# Ring_Controller.net
KiCad netlist of a schematic drawn in EAGLE
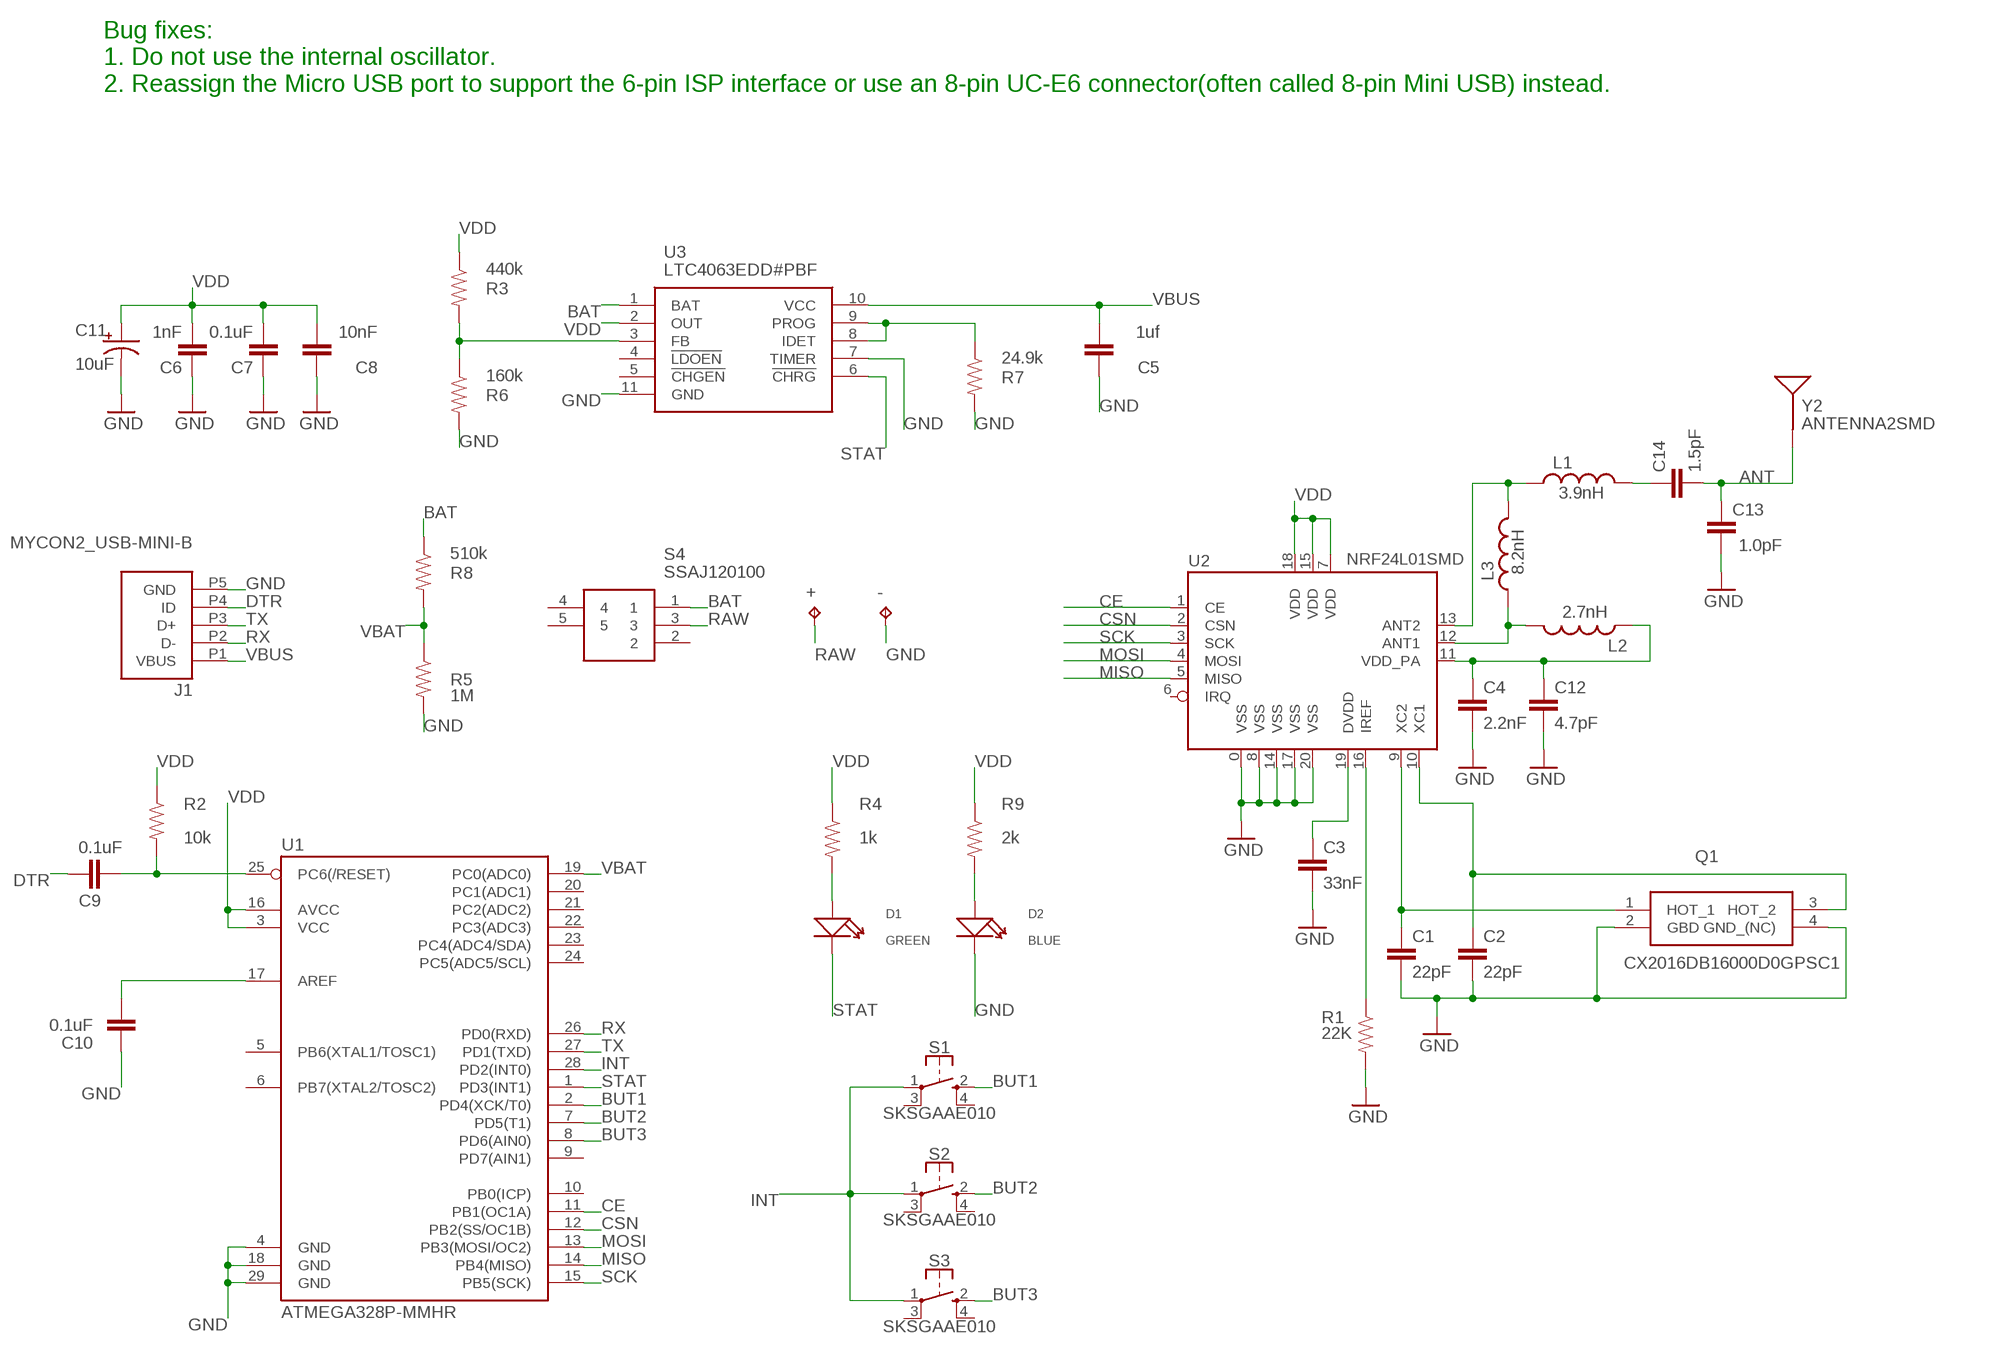
[diagram p0: schematic, sheet 1]

(export (version "E")
  (design (tool "Eeschema 10.0.6"))
  (components
    (comp (ref "+")
      (value "TPB1,27")
      (footprint "eagle-import:B1,27")
      (libsource (lib "eagle-import") (part "TPB1,27"))
    )
    (comp (ref "-")
      (value "TPB1,27")
      (footprint "eagle-import:B1,27")
      (libsource (lib "eagle-import") (part "TPB1,27"))
    )
    (comp (ref "C1")
      (value "22pF")
      (footprint "eagle-import:0402-CAP")
      (libsource (lib "eagle-import") (part "CAP0402-CAP"))
    )
    (comp (ref "C2")
      (value "22pF")
      (footprint "eagle-import:0402-CAP")
      (libsource (lib "eagle-import") (part "CAP0402-CAP"))
    )
    (comp (ref "C3")
      (value "33nF")
      (footprint "eagle-import:0402-CAP")
      (libsource (lib "eagle-import") (part "CAP0402-CAP"))
    )
    (comp (ref "C4")
      (value "2.2nF")
      (footprint "eagle-import:0402-CAP")
      (libsource (lib "eagle-import") (part "CAP0402-CAP"))
    )
    (comp (ref "C5")
      (value "1uf")
      (footprint "eagle-import:0402-CAP")
      (libsource (lib "eagle-import") (part "SparkFun-Passives_CAP0402-CAP"))
    )
    (comp (ref "C6")
      (value "1nF")
      (footprint "eagle-import:0402-CAP")
      (libsource (lib "eagle-import") (part "SparkFun-Passives_CAP0402-CAP"))
    )
    (comp (ref "C7")
      (value "0.1uF")
      (footprint "eagle-import:0402-CAP")
      (libsource (lib "eagle-import") (part "SparkFun-Passives_CAP0402-CAP"))
    )
    (comp (ref "C8")
      (value "10nF")
      (footprint "eagle-import:0402-CAP")
      (libsource (lib "eagle-import") (part "SparkFun-Passives_CAP0402-CAP"))
    )
    (comp (ref "C9")
      (value "0.1uF")
      (footprint "eagle-import:0402-CAP")
      (libsource (lib "eagle-import") (part "SparkFun-Passives_CAP0402-CAP"))
    )
    (comp (ref "C10")
      (value "0.1uF")
      (footprint "eagle-import:0402-CAP")
      (libsource (lib "eagle-import") (part "SparkFun-Passives_CAP0402-CAP"))
    )
    (comp (ref "C11")
      (value "10uF")
      (footprint "eagle-import:0603-POLAR")
      (libsource (lib "eagle-import") (part "10UF-POLAR-0603-6.3V-20%(TANT)"))
    )
    (comp (ref "C12")
      (value "4.7pF")
      (footprint "eagle-import:0402-CAP")
      (libsource (lib "eagle-import") (part "CAP0402-CAP"))
    )
    (comp (ref "C13")
      (value "1.0pF")
      (footprint "eagle-import:0402-CAP")
      (libsource (lib "eagle-import") (part "CAP0402-CAP"))
    )
    (comp (ref "C14")
      (value "1.5pF")
      (footprint "eagle-import:0402-CAP")
      (libsource (lib "eagle-import") (part "CAP0402-CAP"))
    )
    (comp (ref "D1")
      (value "GREEN")
      (footprint "eagle-import:LED-0402")
      (fields (field (name "MPN") "BL-HB337A-AV-TRB"))
      (libsource (lib "eagle-import") (part "SMD-LED-CLEAR-BLUE(0402)"))
    )
    (comp (ref "D2")
      (value "BLUE")
      (footprint "eagle-import:LED-0402")
      (fields (field (name "MPN") "BL-HB337A-AV-TRB"))
      (libsource (lib "eagle-import") (part "SMD-LED-CLEAR-BLUE(0402)"))
    )
    (comp (ref "J1")
      (value "MYCON2_USB-MINI-B")
      (footprint "eagle-import:CON2_USB_MICRO_B_AT")
      (fields (field (name "SPICEPREFIX") "X"))
      (libsource (lib "eagle-import") (part "MYCON2_USB-MINI-B"))
    )
    (comp (ref "L1")
      (value "3.9nH")
      (footprint "eagle-import:C0402")
      (libsource (lib "eagle-import") (part "INDUCTOR0402"))
    )
    (comp (ref "L2")
      (value "2.7nH")
      (footprint "eagle-import:C0402")
      (libsource (lib "eagle-import") (part "INDUCTOR0402"))
    )
    (comp (ref "L3")
      (value "8.2nH")
      (footprint "eagle-import:C0402")
      (libsource (lib "eagle-import") (part "INDUCTOR0402"))
    )
    (comp (ref "Q1")
      (value "CX2016DB16000D0GPSC1")
      (footprint "eagle-import:CX2016DB_1")
      (fields (field (name "MOUSER_PART_NUMBER") "581-CX2016DB16000DPS"))
      (libsource (lib "eagle-import") (part "CX2016DB16000D0GPSC1"))
    )
    (comp (ref "R1")
      (value "22K")
      (footprint "eagle-import:0402-RES")
      (libsource (lib "eagle-import") (part "RESISTOR0402-RES"))
    )
    (comp (ref "R2")
      (value "10k")
      (footprint "eagle-import:0402-RES")
      (libsource (lib "eagle-import") (part "RESISTOR0402"))
    )
    (comp (ref "R3")
      (value "440k")
      (footprint "eagle-import:0402-RES")
      (libsource (lib "eagle-import") (part "RESISTOR0402"))
    )
    (comp (ref "R4")
      (value "1k")
      (footprint "eagle-import:0402-RES")
      (libsource (lib "eagle-import") (part "RESISTOR0402"))
    )
    (comp (ref "R5")
      (value "1M")
      (footprint "eagle-import:0402-RES")
      (libsource (lib "eagle-import") (part "RESISTOR0402"))
    )
    (comp (ref "R6")
      (value "160k")
      (footprint "eagle-import:0402-RES")
      (libsource (lib "eagle-import") (part "RESISTOR0402"))
    )
    (comp (ref "R7")
      (value "24.9k")
      (footprint "eagle-import:0402-RES")
      (libsource (lib "eagle-import") (part "RESISTOR0402"))
    )
    (comp (ref "R8")
      (value "510k")
      (footprint "eagle-import:0402-RES")
      (libsource (lib "eagle-import") (part "RESISTOR0402"))
    )
    (comp (ref "R9")
      (value "2k")
      (footprint "eagle-import:0402-RES")
      (libsource (lib "eagle-import") (part "RESISTOR0402"))
    )
    (comp (ref "S1")
      (value "SKSGAAE010")
      (footprint "eagle-import:SKSG")
      (fields (field (name "MOUSER_PART_NUMBER") "688-SKSGAAE010"))
      (libsource (lib "eagle-import") (part "SKSGAAE010"))
    )
    (comp (ref "S2")
      (value "SKSGAAE010")
      (footprint "eagle-import:SKSG")
      (fields (field (name "MOUSER_PART_NUMBER") "688-SKSGAAE010"))
      (libsource (lib "eagle-import") (part "SKSGAAE010"))
    )
    (comp (ref "S3")
      (value "SKSGAAE010")
      (footprint "eagle-import:SKSG")
      (fields (field (name "MOUSER_PART_NUMBER") "688-SKSGAAE010"))
      (libsource (lib "eagle-import") (part "SKSGAAE010"))
    )
    (comp (ref "S4")
      (value "SSAJ120100")
      (footprint "eagle-import:SSAJ120100")
      (fields (field (name "MOUSER_PART_NUMBER") "688-SSAJ120100") (field (name "RS_PART_NUMBER") "1238892"))
      (libsource (lib "eagle-import") (part "SSAJ120100"))
    )
    (comp (ref "U1")
      (value "ATMEGA328P-MMHR")
      (footprint "eagle-import:QFN45P400X400X100-29N")
      (fields (field (name "MOUSER_PART_NUMBER") "556-ATMEGA328P-MMHR"))
      (libsource (lib "eagle-import") (part "ATMEGA328P-MMHR"))
    )
    (comp (ref "U2")
      (value "NRF24L01SMD")
      (footprint "eagle-import:QFN20-4X4MM")
      (libsource (lib "eagle-import") (part "NRF24L01SMD"))
    )
    (comp (ref "U3")
      (value "LTC4063EDD#PBF")
      (footprint "eagle-import:SON50P300X300X80-11N")
      (fields (field (name "MOUSER_PART_NUMBER") "584-LTC4063EDD#PBF"))
      (libsource (lib "eagle-import") (part "LTC4063EDD#PBF"))
    )
    (comp (ref "Y2")
      (value "ANTENNA2SMD")
      (footprint "eagle-import:ANTENNA-CHIP2")
      (libsource (lib "eagle-import") (part "ANTENNA2SMD"))
    )
  )
  (nets
    (net (code "1") (name "/ANT") (class "Default")
      (node (ref "C13") (pin "2") (pinfunction "2_2") (pintype "passive"))
      (node (ref "C14") (pin "2") (pinfunction "2_2") (pintype "passive"))
      (node (ref "Y2") (pin "FEED") (pinfunction "SIGNAL_FEED") (pintype "bidirectional"))
    )
    (net (code "2") (name "/BAT") (class "Default")
      (node (ref "R8") (pin "1") (pinfunction "1_1") (pintype "passive"))
      (node (ref "S4") (pin "1") (pinfunction "1_1") (pintype "bidirectional"))
      (node (ref "U3") (pin "1") (pinfunction "BAT_1") (pintype "bidirectional"))
    )
    (net (code "3") (name "/BUT1") (class "Default")
      (node (ref "S1") (pin "2") (pinfunction "3_2") (pintype "passive"))
      (node (ref "U1") (pin "2") (pinfunction "PD4(XCK/T0)_2") (pintype "bidirectional"))
    )
    (net (code "4") (name "/BUT2") (class "Default")
      (node (ref "S2") (pin "2") (pinfunction "3_2") (pintype "passive"))
      (node (ref "U1") (pin "7") (pinfunction "PD5(T1)_7") (pintype "bidirectional"))
    )
    (net (code "5") (name "/BUT3") (class "Default")
      (node (ref "S3") (pin "2") (pinfunction "3_2") (pintype "passive"))
      (node (ref "U1") (pin "8") (pinfunction "PD6(AIN0)_8") (pintype "bidirectional"))
    )
    (net (code "6") (name "/CE") (class "Default")
      (node (ref "U1") (pin "11") (pinfunction "PB1(OC1A)_11") (pintype "bidirectional"))
      (node (ref "U2") (pin "1") (pinfunction "CE_1") (pintype "input"))
    )
    (net (code "7") (name "/CSN") (class "Default")
      (node (ref "U1") (pin "12") (pinfunction "PB2(SS/OC1B)_12") (pintype "bidirectional"))
      (node (ref "U2") (pin "2") (pinfunction "CSN_2") (pintype "input"))
    )
    (net (code "8") (name "/DTR") (class "Default")
      (node (ref "C9") (pin "1") (pinfunction "1_1") (pintype "passive"))
      (node (ref "J1") (pin "P4") (pinfunction "ID_P4") (pintype "bidirectional"))
    )
    (net (code "9") (name "/INT") (class "Default")
      (node (ref "S1") (pin "1") (pinfunction "1_1") (pintype "passive"))
      (node (ref "S2") (pin "1") (pinfunction "1_1") (pintype "passive"))
      (node (ref "S3") (pin "1") (pinfunction "1_1") (pintype "passive"))
      (node (ref "U1") (pin "28") (pinfunction "PD2(INT0)_28") (pintype "bidirectional"))
    )
    (net (code "10") (name "/MISO") (class "Default")
      (node (ref "U1") (pin "14") (pinfunction "PB4(MISO)_14") (pintype "bidirectional"))
      (node (ref "U2") (pin "5") (pinfunction "MISO_5") (pintype "output"))
    )
    (net (code "11") (name "/MOSI") (class "Default")
      (node (ref "U1") (pin "13") (pinfunction "PB3(MOSI/OC2)_13") (pintype "bidirectional"))
      (node (ref "U2") (pin "4") (pinfunction "MOSI_4") (pintype "input"))
    )
    (net (code "12") (name "/RAW") (class "Default")
      (node (ref "+") (pin "TP") (pinfunction "TP_TP") (pintype "input"))
      (node (ref "S4") (pin "3") (pinfunction "3_3") (pintype "bidirectional"))
    )
    (net (code "13") (name "/RX") (class "Default")
      (node (ref "J1") (pin "P2") (pinfunction "D-_P2") (pintype "bidirectional"))
      (node (ref "U1") (pin "26") (pinfunction "PD0(RXD)_26") (pintype "bidirectional"))
    )
    (net (code "14") (name "/SCK") (class "Default")
      (node (ref "U1") (pin "15") (pinfunction "PB5(SCK)_15") (pintype "bidirectional"))
      (node (ref "U2") (pin "3") (pinfunction "SCK_3") (pintype "input"))
    )
    (net (code "15") (name "/STAT") (class "Default")
      (node (ref "D1") (pin "-") (pinfunction "-_-") (pintype "passive"))
      (node (ref "U1") (pin "1") (pinfunction "PD3(INT1)_1") (pintype "bidirectional"))
      (node (ref "U3") (pin "6") (pinfunction "~{CHRG}_6") (pintype "bidirectional"))
    )
    (net (code "16") (name "/TX") (class "Default")
      (node (ref "J1") (pin "P3") (pinfunction "D+_P3") (pintype "bidirectional"))
      (node (ref "U1") (pin "27") (pinfunction "PD1(TXD)_27") (pintype "bidirectional"))
    )
    (net (code "17") (name "/VBAT") (class "Default")
      (node (ref "R5") (pin "1") (pinfunction "1_1") (pintype "passive"))
      (node (ref "R8") (pin "2") (pinfunction "2_2") (pintype "passive"))
      (node (ref "U1") (pin "19") (pinfunction "PC0(ADC0)_19") (pintype "bidirectional"))
    )
    (net (code "18") (name "/VBUS") (class "Default")
      (node (ref "C5") (pin "2") (pinfunction "2_2") (pintype "passive"))
      (node (ref "J1") (pin "P1") (pinfunction "VBUS_P1") (pintype "power_in"))
      (node (ref "U3") (pin "10") (pinfunction "VCC_10") (pintype "bidirectional"))
    )
    (net (code "19") (name "/VDD") (class "Default")
      (node (ref "C11") (pin "+") (pinfunction "+_+") (pintype "passive"))
      (node (ref "C6") (pin "2") (pinfunction "2_2") (pintype "passive"))
      (node (ref "C7") (pin "2") (pinfunction "2_2") (pintype "passive"))
      (node (ref "C8") (pin "2") (pinfunction "2_2") (pintype "passive"))
      (node (ref "R2") (pin "1") (pinfunction "1_1") (pintype "passive"))
      (node (ref "R3") (pin "1") (pinfunction "1_1") (pintype "passive"))
      (node (ref "R4") (pin "1") (pinfunction "1_1") (pintype "passive"))
      (node (ref "R9") (pin "1") (pinfunction "1_1") (pintype "passive"))
      (node (ref "U1") (pin "16") (pinfunction "AVCC_16") (pintype "bidirectional"))
      (node (ref "U1") (pin "3") (pinfunction "VCC_3") (pintype "bidirectional"))
      (node (ref "U2") (pin "15") (pinfunction "VDD_15") (pintype "power_in"))
      (node (ref "U2") (pin "18") (pinfunction "VDD_18") (pintype "power_in"))
      (node (ref "U2") (pin "7") (pinfunction "VDD_7") (pintype "power_in"))
      (node (ref "U3") (pin "2") (pinfunction "OUT_2") (pintype "bidirectional"))
    )
    (net (code "20") (name "GND") (class "Default")
      (node (ref "-") (pin "TP") (pinfunction "TP_TP") (pintype "input"))
      (node (ref "C1") (pin "2") (pinfunction "2_2") (pintype "passive"))
      (node (ref "C10") (pin "1") (pinfunction "1_1") (pintype "passive"))
      (node (ref "C11") (pin "-") (pinfunction "-_-") (pintype "passive"))
      (node (ref "C12") (pin "2") (pinfunction "2_2") (pintype "passive"))
      (node (ref "C13") (pin "1") (pinfunction "1_1") (pintype "passive"))
      (node (ref "C2") (pin "2") (pinfunction "2_2") (pintype "passive"))
      (node (ref "C3") (pin "2") (pinfunction "2_2") (pintype "passive"))
      (node (ref "C4") (pin "2") (pinfunction "2_2") (pintype "passive"))
      (node (ref "C5") (pin "1") (pinfunction "1_1") (pintype "passive"))
      (node (ref "C6") (pin "1") (pinfunction "1_1") (pintype "passive"))
      (node (ref "C7") (pin "1") (pinfunction "1_1") (pintype "passive"))
      (node (ref "C8") (pin "1") (pinfunction "1_1") (pintype "passive"))
      (node (ref "D2") (pin "-") (pinfunction "-_-") (pintype "passive"))
      (node (ref "J1") (pin "P5") (pinfunction "GND_P5") (pintype "passive"))
      (node (ref "Q1") (pin "2") (pinfunction "GBD_2") (pintype "bidirectional"))
      (node (ref "Q1") (pin "4") (pinfunction "GND_(NC)_4") (pintype "bidirectional"))
      (node (ref "R1") (pin "2") (pinfunction "2_2") (pintype "passive"))
      (node (ref "R5") (pin "2") (pinfunction "2_2") (pintype "passive"))
      (node (ref "R6") (pin "2") (pinfunction "2_2") (pintype "passive"))
      (node (ref "R7") (pin "2") (pinfunction "2_2") (pintype "passive"))
      (node (ref "U1") (pin "18") (pinfunction "GND_18") (pintype "bidirectional"))
      (node (ref "U1") (pin "29") (pinfunction "GND_29") (pintype "bidirectional"))
      (node (ref "U1") (pin "4") (pinfunction "GND_4") (pintype "bidirectional"))
      (node (ref "U2") (pin "0") (pinfunction "VSS_0") (pintype "power_in"))
      (node (ref "U2") (pin "14") (pinfunction "VSS_14") (pintype "power_in"))
      (node (ref "U2") (pin "17") (pinfunction "VSS_17") (pintype "power_in"))
      (node (ref "U2") (pin "20") (pinfunction "VSS_20") (pintype "power_in"))
      (node (ref "U2") (pin "8") (pinfunction "VSS_8") (pintype "power_in"))
      (node (ref "U3") (pin "11") (pinfunction "GND_11") (pintype "bidirectional"))
      (node (ref "U3") (pin "7") (pinfunction "TIMER_7") (pintype "bidirectional"))
    )
    (net (code "21") (name "Net-(C14-Pad1)") (class "Default")
      (node (ref "C14") (pin "1") (pinfunction "1_1") (pintype "passive"))
      (node (ref "L1") (pin "2") (pinfunction "2_2") (pintype "passive"))
    )
    (net (code "22") (name "Net-(D1-Pad+)") (class "Default")
      (node (ref "D1") (pin "+") (pinfunction "+_+") (pintype "passive"))
      (node (ref "R4") (pin "2") (pinfunction "2_2") (pintype "passive"))
    )
    (net (code "23") (name "Net-(D2-Pad+)") (class "Default")
      (node (ref "D2") (pin "+") (pinfunction "+_+") (pintype "passive"))
      (node (ref "R9") (pin "2") (pinfunction "2_2") (pintype "passive"))
    )
    (net (code "24") (name "Net-(Q1-HOT_1)") (class "Default")
      (node (ref "C1") (pin "1") (pinfunction "1_1") (pintype "passive"))
      (node (ref "Q1") (pin "1") (pinfunction "HOT_1_1") (pintype "bidirectional"))
      (node (ref "U2") (pin "9") (pinfunction "XC2_9") (pintype "input"))
    )
    (net (code "25") (name "Net-(Q1-HOT_2)") (class "Default")
      (node (ref "C2") (pin "1") (pinfunction "1_1") (pintype "passive"))
      (node (ref "Q1") (pin "3") (pinfunction "HOT_2_3") (pintype "bidirectional"))
      (node (ref "U2") (pin "10") (pinfunction "XC1_10") (pintype "input"))
    )
    (net (code "26") (name "Net-(U1-AREF)") (class "Default")
      (node (ref "C10") (pin "2") (pinfunction "2_2") (pintype "passive"))
      (node (ref "U1") (pin "17") (pinfunction "AREF_17") (pintype "bidirectional"))
    )
    (net (code "27") (name "Net-(U1-PC6({slash}RESET))") (class "Default")
      (node (ref "C9") (pin "2") (pinfunction "2_2") (pintype "passive"))
      (node (ref "R2") (pin "2") (pinfunction "2_2") (pintype "passive"))
      (node (ref "U1") (pin "25") (pinfunction "PC6(/RESET)_25") (pintype "bidirectional"))
    )
    (net (code "28") (name "Net-(U2-ANT1)") (class "Default")
      (node (ref "L2") (pin "2") (pinfunction "2_2") (pintype "passive"))
      (node (ref "L3") (pin "1") (pinfunction "1_1") (pintype "passive"))
      (node (ref "U2") (pin "12") (pinfunction "ANT1_12") (pintype "output"))
    )
    (net (code "29") (name "Net-(U2-ANT2)") (class "Default")
      (node (ref "L1") (pin "1") (pinfunction "1_1") (pintype "passive"))
      (node (ref "L3") (pin "2") (pinfunction "2_2") (pintype "passive"))
      (node (ref "U2") (pin "13") (pinfunction "ANT2_13") (pintype "output"))
    )
    (net (code "30") (name "Net-(U2-DVDD)") (class "Default")
      (node (ref "C3") (pin "1") (pinfunction "1_1") (pintype "passive"))
      (node (ref "U2") (pin "19") (pinfunction "DVDD_19") (pintype "power_in"))
    )
    (net (code "31") (name "Net-(U2-IREF)") (class "Default")
      (node (ref "R1") (pin "1") (pinfunction "1_1") (pintype "passive"))
      (node (ref "U2") (pin "16") (pinfunction "IREF_16") (pintype "input"))
    )
    (net (code "32") (name "Net-(U2-VDD_PA)") (class "Default")
      (node (ref "C12") (pin "1") (pinfunction "1_1") (pintype "passive"))
      (node (ref "C4") (pin "1") (pinfunction "1_1") (pintype "passive"))
      (node (ref "L2") (pin "1") (pinfunction "1_1") (pintype "passive"))
      (node (ref "U2") (pin "11") (pinfunction "VDD_PA_11") (pintype "power_in"))
    )
    (net (code "33") (name "Net-(U3-FB)") (class "Default")
      (node (ref "R3") (pin "2") (pinfunction "2_2") (pintype "passive"))
      (node (ref "R6") (pin "1") (pinfunction "1_1") (pintype "passive"))
      (node (ref "U3") (pin "3") (pinfunction "FB_3") (pintype "bidirectional"))
    )
    (net (code "34") (name "Net-(U3-IDET)") (class "Default")
      (node (ref "R7") (pin "1") (pinfunction "1_1") (pintype "passive"))
      (node (ref "U3") (pin "8") (pinfunction "IDET_8") (pintype "bidirectional"))
      (node (ref "U3") (pin "9") (pinfunction "PROG_9") (pintype "bidirectional"))
    )
    (net (code "35") (name "unconnected-(S1-2-Pad3)") (class "Default")
      (node (ref "S1") (pin "3") (pinfunction "2_3") (pintype "passive"))
    )
    (net (code "36") (name "unconnected-(S1-Pad4)") (class "Default")
      (node (ref "S1") (pin "4") (pinfunction "4_4") (pintype "passive"))
    )
    (net (code "37") (name "unconnected-(S2-2-Pad3)") (class "Default")
      (node (ref "S2") (pin "3") (pinfunction "2_3") (pintype "passive"))
    )
    (net (code "38") (name "unconnected-(S2-Pad4)") (class "Default")
      (node (ref "S2") (pin "4") (pinfunction "4_4") (pintype "passive"))
    )
    (net (code "39") (name "unconnected-(S3-2-Pad3)") (class "Default")
      (node (ref "S3") (pin "3") (pinfunction "2_3") (pintype "passive"))
    )
    (net (code "40") (name "unconnected-(S3-Pad4)") (class "Default")
      (node (ref "S3") (pin "4") (pinfunction "4_4") (pintype "passive"))
    )
    (net (code "41") (name "unconnected-(S4-Pad2)") (class "Default")
      (node (ref "S4") (pin "2") (pinfunction "2_2") (pintype "bidirectional"))
    )
    (net (code "42") (name "unconnected-(S4-Pad4)") (class "Default")
      (node (ref "S4") (pin "4") (pinfunction "4_4") (pintype "bidirectional"))
    )
    (net (code "43") (name "unconnected-(S4-Pad5)") (class "Default")
      (node (ref "S4") (pin "5") (pinfunction "5_5") (pintype "bidirectional"))
    )
    (net (code "44") (name "unconnected-(U1-PB0(ICP)-Pad10)") (class "Default")
      (node (ref "U1") (pin "10") (pinfunction "PB0(ICP)_10") (pintype "bidirectional"))
    )
    (net (code "45") (name "unconnected-(U1-PB6(XTAL1{slash}TOSC1)-Pad5)") (class "Default")
      (node (ref "U1") (pin "5") (pinfunction "PB6(XTAL1/TOSC1)_5") (pintype "bidirectional"))
    )
    (net (code "46") (name "unconnected-(U1-PB7(XTAL2{slash}TOSC2)-Pad6)") (class "Default")
      (node (ref "U1") (pin "6") (pinfunction "PB7(XTAL2/TOSC2)_6") (pintype "bidirectional"))
    )
    (net (code "47") (name "unconnected-(U1-PC1(ADC1)-Pad20)") (class "Default")
      (node (ref "U1") (pin "20") (pinfunction "PC1(ADC1)_20") (pintype "bidirectional"))
    )
    (net (code "48") (name "unconnected-(U1-PC2(ADC2)-Pad21)") (class "Default")
      (node (ref "U1") (pin "21") (pinfunction "PC2(ADC2)_21") (pintype "bidirectional"))
    )
    (net (code "49") (name "unconnected-(U1-PC3(ADC3)-Pad22)") (class "Default")
      (node (ref "U1") (pin "22") (pinfunction "PC3(ADC3)_22") (pintype "bidirectional"))
    )
    (net (code "50") (name "unconnected-(U1-PC4(ADC4{slash}SDA)-Pad23)") (class "Default")
      (node (ref "U1") (pin "23") (pinfunction "PC4(ADC4/SDA)_23") (pintype "bidirectional"))
    )
    (net (code "51") (name "unconnected-(U1-PC5(ADC5{slash}SCL)-Pad24)") (class "Default")
      (node (ref "U1") (pin "24") (pinfunction "PC5(ADC5/SCL)_24") (pintype "bidirectional"))
    )
    (net (code "52") (name "unconnected-(U1-PD7(AIN1)-Pad9)") (class "Default")
      (node (ref "U1") (pin "9") (pinfunction "PD7(AIN1)_9") (pintype "bidirectional"))
    )
    (net (code "53") (name "unconnected-(U2-IRQ-Pad6)") (class "Default")
      (node (ref "U2") (pin "6") (pinfunction "IRQ_6") (pintype "output"))
    )
    (net (code "54") (name "unconnected-(U3-~{CHGEN}-Pad5)") (class "Default")
      (node (ref "U3") (pin "5") (pinfunction "~{CHGEN}_5") (pintype "bidirectional"))
    )
    (net (code "55") (name "unconnected-(U3-~{LDOEN}-Pad4)") (class "Default")
      (node (ref "U3") (pin "4") (pinfunction "~{LDOEN}_4") (pintype "bidirectional"))
    )
  )
)
